# Connector.net
KiCad netlist of a schematic drawn in Altium Designer
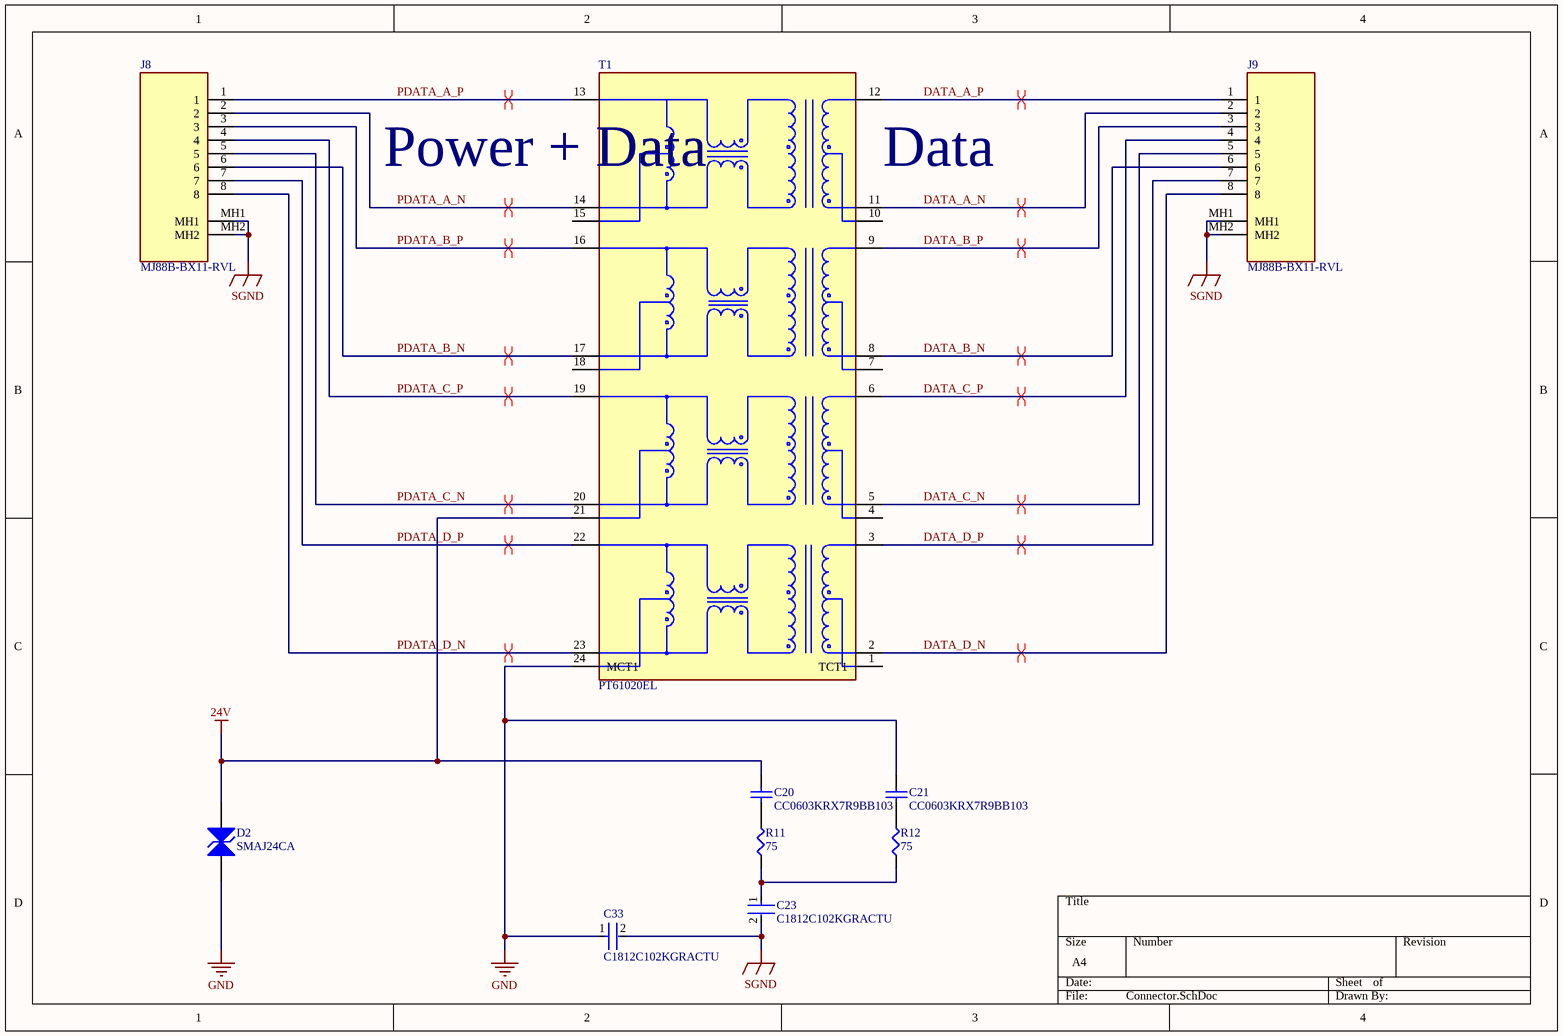
[diagram p0: Connector.SchDoc]

(export (version "E")
  (design (tool "Eeschema 10.0.6"))
  (components
    (comp (ref "C20")
      (value "CC0603KRX7R9BB103")
      (footprint "CAPC1608X90X40ML10T20")
      (description "Chip Capacitor, 10 nF, +/- 10%, 50 V, -55 to 125 degC, 0603 (1608 Metric), RoHS, Tape and Reel")
      (fields (field (name "MANUFACTURER") "Yageo") (field (name "TOLERANCE") "10%"))
      (libsource (lib "Altium Content Vault") (part "CAP-NP-2"))
    )
    (comp (ref "C21")
      (value "CC0603KRX7R9BB103")
      (footprint "CAPC1608X90X40ML10T20")
      (description "Chip Capacitor, 10 nF, +/- 10%, 50 V, -55 to 125 degC, 0603 (1608 Metric), RoHS, Tape and Reel")
      (fields (field (name "MANUFACTURER") "Yageo") (field (name "TOLERANCE") "10%"))
      (libsource (lib "Altium Content Vault") (part "CAP-NP-2"))
    )
    (comp (ref "C23")
      (value "C1812C102KGRACTU")
      (footprint "FP-C1812C102KGRACTU-MFG")
      (description "CAP CER 1000PF 2KV X7R 1812")
      (libsource (lib "Altium Content Vault") (part "02cd4be3c70576c341d710602a673aa"))
    )
    (comp (ref "C33")
      (value "C1812C102KGRACTU")
      (footprint "FP-C1812C102KGRACTU-MFG")
      (description "CAP CER 1000PF 2KV X7R 1812")
      (libsource (lib "Altium Content Vault") (part "02cd4be3c70576c341d710602a673aa"))
    )
    (comp (ref "D2")
      (value "SMAJ24CA")
      (footprint "LFUS-DO-214AC-A-2_L")
      (description "Transient Voltage Suppression Diode, 400 W, 24 V, -65 to 150 degC, 2-Pin SMD, RoHS, Tape and Reel")
      (fields (field (name "MANUFACTURER") "Littelfuse"))
      (libsource (lib "Altium Content Vault") (part "DZEN-AA-2"))
    )
    (comp (ref "J8")
      (value "MJ88B-BX11-RVL")
      (footprint "MJ88B-BX11-RVL")
      (description "Modular Jack, 8P8C, Straddle DIP")
      (libsource (lib "DrvBoard") (part "MJ88B-BX11-RVL"))
    )
    (comp (ref "J9")
      (value "MJ88B-BX11-RVL")
      (footprint "MJ88B-BX11-RVL")
      (description "Modular Jack, 8P8C, Straddle DIP")
      (libsource (lib "") (part "MJ88B-BX11-RVL_1"))
    )
    (comp (ref "R11")
      (value "75")
      (footprint "SMD-0603-RES")
      (description "RES SMD 75 OHM 1% 1/10W 0603")
      (fields
        (field (name "PART NUMBER") "ERJ-3EKF75R0V")
        (field (name "DIGI-KEY PART NUMBER") "P75.0HCT-ND")
      )
      (libsource (lib "Panasonic_ERJ_0603") (part "ERJ-3EKF75R0V"))
    )
    (comp (ref "R12")
      (value "75")
      (footprint "SMD-0603-RES")
      (description "RES SMD 75 OHM 1% 1/10W 0603")
      (fields
        (field (name "PART NUMBER") "ERJ-3EKF75R0V")
        (field (name "DIGI-KEY PART NUMBER") "P75.0HCT-ND")
      )
      (libsource (lib "Panasonic_ERJ_0603") (part "ERJ-3EKF75R0V"))
    )
    (comp (ref "T1")
      (value "PT61020EL")
      (footprint "FP-PT61020EL-MFG")
      (description "PULSE XFMR 1CT:1 350UH")
      (libsource (lib "Altium Content Vault") (part "de6672f9622ecadc0b676d1c5e05dad"))
    )
  )
  (nets
    (net (code "1") (name "/DATA_A_N") (class "Default")
      (node (ref "J9") (pin "2") (pinfunction "2_2") (pintype "passive"))
      (node (ref "T1") (pin "11") (pinfunction "TD4+_11") (pintype "passive"))
    )
    (net (code "2") (name "/DATA_A_P") (class "Default")
      (node (ref "J9") (pin "1") (pinfunction "1_1") (pintype "passive"))
      (node (ref "T1") (pin "12") (pinfunction "TD4-_12") (pintype "passive"))
    )
    (net (code "3") (name "/DATA_B_N") (class "Default")
      (node (ref "J9") (pin "6") (pinfunction "6_6") (pintype "passive"))
      (node (ref "T1") (pin "8") (pinfunction "TD3+_8") (pintype "passive"))
    )
    (net (code "4") (name "/DATA_B_P") (class "Default")
      (node (ref "J9") (pin "3") (pinfunction "3_3") (pintype "passive"))
      (node (ref "T1") (pin "9") (pinfunction "TD3-_9") (pintype "passive"))
    )
    (net (code "5") (name "/DATA_C_N") (class "Default")
      (node (ref "J9") (pin "5") (pinfunction "5_5") (pintype "passive"))
      (node (ref "T1") (pin "5") (pinfunction "TD2+_5") (pintype "passive"))
    )
    (net (code "6") (name "/DATA_C_P") (class "Default")
      (node (ref "J9") (pin "4") (pinfunction "4_4") (pintype "passive"))
      (node (ref "T1") (pin "6") (pinfunction "TD2-_6") (pintype "passive"))
    )
    (net (code "7") (name "/DATA_D_N") (class "Default")
      (node (ref "J9") (pin "8") (pinfunction "8_8") (pintype "passive"))
      (node (ref "T1") (pin "2") (pinfunction "TD1+_2") (pintype "passive"))
    )
    (net (code "8") (name "/DATA_D_P") (class "Default")
      (node (ref "J9") (pin "7") (pinfunction "7_7") (pintype "passive"))
      (node (ref "T1") (pin "3") (pinfunction "TD1-_3") (pintype "passive"))
    )
    (net (code "9") (name "/PDATA_A_N") (class "Default")
      (node (ref "J8") (pin "2") (pinfunction "2_2") (pintype "passive"))
      (node (ref "T1") (pin "14") (pinfunction "MX4+_14") (pintype "passive"))
    )
    (net (code "10") (name "/PDATA_A_P") (class "Default")
      (node (ref "J8") (pin "1") (pinfunction "1_1") (pintype "passive"))
      (node (ref "T1") (pin "13") (pinfunction "MX4-_13") (pintype "passive"))
    )
    (net (code "11") (name "/PDATA_B_N") (class "Default")
      (node (ref "J8") (pin "6") (pinfunction "6_6") (pintype "passive"))
      (node (ref "T1") (pin "17") (pinfunction "MX3+_17") (pintype "passive"))
    )
    (net (code "12") (name "/PDATA_B_P") (class "Default")
      (node (ref "J8") (pin "3") (pinfunction "3_3") (pintype "passive"))
      (node (ref "T1") (pin "16") (pinfunction "MX3-_16") (pintype "passive"))
    )
    (net (code "13") (name "/PDATA_C_N") (class "Default")
      (node (ref "J8") (pin "5") (pinfunction "5_5") (pintype "passive"))
      (node (ref "T1") (pin "20") (pinfunction "MX2+_20") (pintype "passive"))
    )
    (net (code "14") (name "/PDATA_C_P") (class "Default")
      (node (ref "J8") (pin "4") (pinfunction "4_4") (pintype "passive"))
      (node (ref "T1") (pin "19") (pinfunction "MX2-_19") (pintype "passive"))
    )
    (net (code "15") (name "/PDATA_D_N") (class "Default")
      (node (ref "J8") (pin "8") (pinfunction "8_8") (pintype "passive"))
      (node (ref "T1") (pin "23") (pinfunction "MX1+_23") (pintype "passive"))
    )
    (net (code "16") (name "/PDATA_D_P") (class "Default")
      (node (ref "J8") (pin "7") (pinfunction "7_7") (pintype "passive"))
      (node (ref "T1") (pin "22") (pinfunction "MX1-_22") (pintype "passive"))
    )
    (net (code "17") (name "24V") (class "Default")
      (node (ref "C20") (pin "2") (pinfunction "2_2") (pintype "passive"))
      (node (ref "D2") (pin "2") (pinfunction "A_2") (pintype "passive"))
      (node (ref "T1") (pin "21") (pinfunction "MCT2_21") (pintype "passive"))
    )
    (net (code "18") (name "GND") (class "Default")
      (node (ref "C21") (pin "2") (pinfunction "2_2") (pintype "passive"))
      (node (ref "C33") (pin "1") (pinfunction "1_1") (pintype "passive"))
      (node (ref "D2") (pin "1") (pinfunction "A_1") (pintype "passive"))
      (node (ref "T1") (pin "24") (pinfunction "MCT1_24") (pintype "passive"))
    )
    (net (code "19") (name "Net-(C20-Pad1)") (class "Default")
      (node (ref "C20") (pin "1") (pinfunction "1_1") (pintype "passive"))
      (node (ref "R11") (pin "2") (pinfunction "2_2") (pintype "passive"))
    )
    (net (code "20") (name "Net-(C21-Pad1)") (class "Default")
      (node (ref "C21") (pin "1") (pinfunction "1_1") (pintype "passive"))
      (node (ref "R12") (pin "2") (pinfunction "2_2") (pintype "passive"))
    )
    (net (code "21") (name "Net-(C23-Pad1)") (class "Default")
      (node (ref "C23") (pin "1") (pinfunction "1_1") (pintype "passive"))
      (node (ref "R11") (pin "1") (pinfunction "1_1") (pintype "passive"))
      (node (ref "R12") (pin "1") (pinfunction "1_1") (pintype "passive"))
    )
    (net (code "22") (name "SGND") (class "Default")
      (node (ref "C23") (pin "2") (pinfunction "2_2") (pintype "passive"))
      (node (ref "C33") (pin "2") (pinfunction "2_2") (pintype "passive"))
      (node (ref "J8") (pin "MH1") (pinfunction "MH1_MH1") (pintype "passive"))
      (node (ref "J8") (pin "MH2") (pinfunction "MH2_MH2") (pintype "passive"))
      (node (ref "J9") (pin "MH1") (pinfunction "MH1_MH1") (pintype "passive"))
      (node (ref "J9") (pin "MH2") (pinfunction "MH2_MH2") (pintype "passive"))
    )
    (net (code "23") (name "unconnected-(T1-MCT3-Pad18)") (class "Default")
      (node (ref "T1") (pin "18") (pinfunction "MCT3_18") (pintype "passive"))
    )
    (net (code "24") (name "unconnected-(T1-MCT4-Pad15)") (class "Default")
      (node (ref "T1") (pin "15") (pinfunction "MCT4_15") (pintype "passive"))
    )
    (net (code "25") (name "unconnected-(T1-TCT1-Pad1)") (class "Default")
      (node (ref "T1") (pin "1") (pinfunction "TCT1_1") (pintype "passive"))
    )
    (net (code "26") (name "unconnected-(T1-TCT2-Pad4)") (class "Default")
      (node (ref "T1") (pin "4") (pinfunction "TCT2_4") (pintype "passive"))
    )
    (net (code "27") (name "unconnected-(T1-TCT3-Pad7)") (class "Default")
      (node (ref "T1") (pin "7") (pinfunction "TCT3_7") (pintype "passive"))
    )
    (net (code "28") (name "unconnected-(T1-TCT4-Pad10)") (class "Default")
      (node (ref "T1") (pin "10") (pinfunction "TCT4_10") (pintype "passive"))
    )
  )
)
